# Dash_LEDs_r3.net
KiCad netlist of a schematic drawn in EAGLE
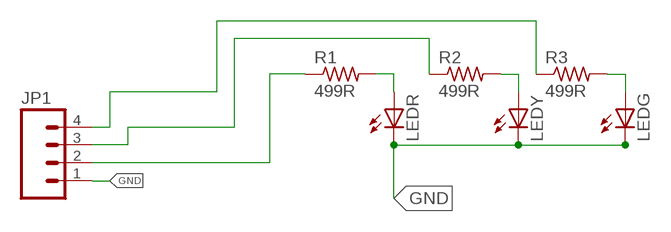
[diagram p0: schematic, sheet 1]

(export (version "E")
  (design (tool "Eeschema 10.0.6"))
  (components
    (comp (ref "JP1")
      (value "M04PTH")
      (footprint "eagle-import:1X04")
      (libsource (lib "eagle-import") (part "M04PTH"))
    )
    (comp (ref "LEDG")
      (value "LED5MM")
      (footprint "eagle-import:LED5MM")
      (libsource (lib "eagle-import") (part "LED5MM"))
    )
    (comp (ref "LEDR")
      (value "LED5MM")
      (footprint "eagle-import:LED5MM")
      (libsource (lib "eagle-import") (part "LED5MM"))
    )
    (comp (ref "LEDY")
      (value "LED5MM")
      (footprint "eagle-import:LED5MM")
      (libsource (lib "eagle-import") (part "LED5MM"))
    )
    (comp (ref "R1")
      (value "499R")
      (footprint "eagle-import:R0805")
      (libsource (lib "eagle-import") (part "R-US_R0805"))
    )
    (comp (ref "R2")
      (value "499R")
      (footprint "eagle-import:R0805")
      (libsource (lib "eagle-import") (part "R-US_R0805"))
    )
    (comp (ref "R3")
      (value "499R")
      (footprint "eagle-import:R0805")
      (libsource (lib "eagle-import") (part "R-US_R0805"))
    )
  )
  (nets
    (net (code "1") (name "GND") (class "Default")
      (node (ref "JP1") (pin "1") (pinfunction "1_1") (pintype "passive"))
      (node (ref "LEDG") (pin "K") (pinfunction "C_K") (pintype "passive"))
      (node (ref "LEDR") (pin "K") (pinfunction "C_K") (pintype "passive"))
      (node (ref "LEDY") (pin "K") (pinfunction "C_K") (pintype "passive"))
    )
    (net (code "2") (name "Net-(JP1-Pad2)") (class "Default")
      (node (ref "JP1") (pin "2") (pinfunction "2_2") (pintype "passive"))
      (node (ref "R1") (pin "1") (pinfunction "1_1") (pintype "passive"))
    )
    (net (code "3") (name "Net-(JP1-Pad3)") (class "Default")
      (node (ref "JP1") (pin "3") (pinfunction "3_3") (pintype "passive"))
      (node (ref "R2") (pin "1") (pinfunction "1_1") (pintype "passive"))
    )
    (net (code "4") (name "Net-(JP1-Pad4)") (class "Default")
      (node (ref "JP1") (pin "4") (pinfunction "4_4") (pintype "passive"))
      (node (ref "R3") (pin "1") (pinfunction "1_1") (pintype "passive"))
    )
    (net (code "5") (name "Net-(LEDG-PadA)") (class "Default")
      (node (ref "LEDG") (pin "A") (pinfunction "A_A") (pintype "passive"))
      (node (ref "R3") (pin "2") (pinfunction "2_2") (pintype "passive"))
    )
    (net (code "6") (name "Net-(LEDR-PadA)") (class "Default")
      (node (ref "LEDR") (pin "A") (pinfunction "A_A") (pintype "passive"))
      (node (ref "R1") (pin "2") (pinfunction "2_2") (pintype "passive"))
    )
    (net (code "7") (name "Net-(LEDY-PadA)") (class "Default")
      (node (ref "LEDY") (pin "A") (pinfunction "A_A") (pintype "passive"))
      (node (ref "R2") (pin "2") (pinfunction "2_2") (pintype "passive"))
    )
  )
)
